# Power_Supply_Signal_Conditioning.net
KiCad netlist of a schematic drawn in Altium Designer
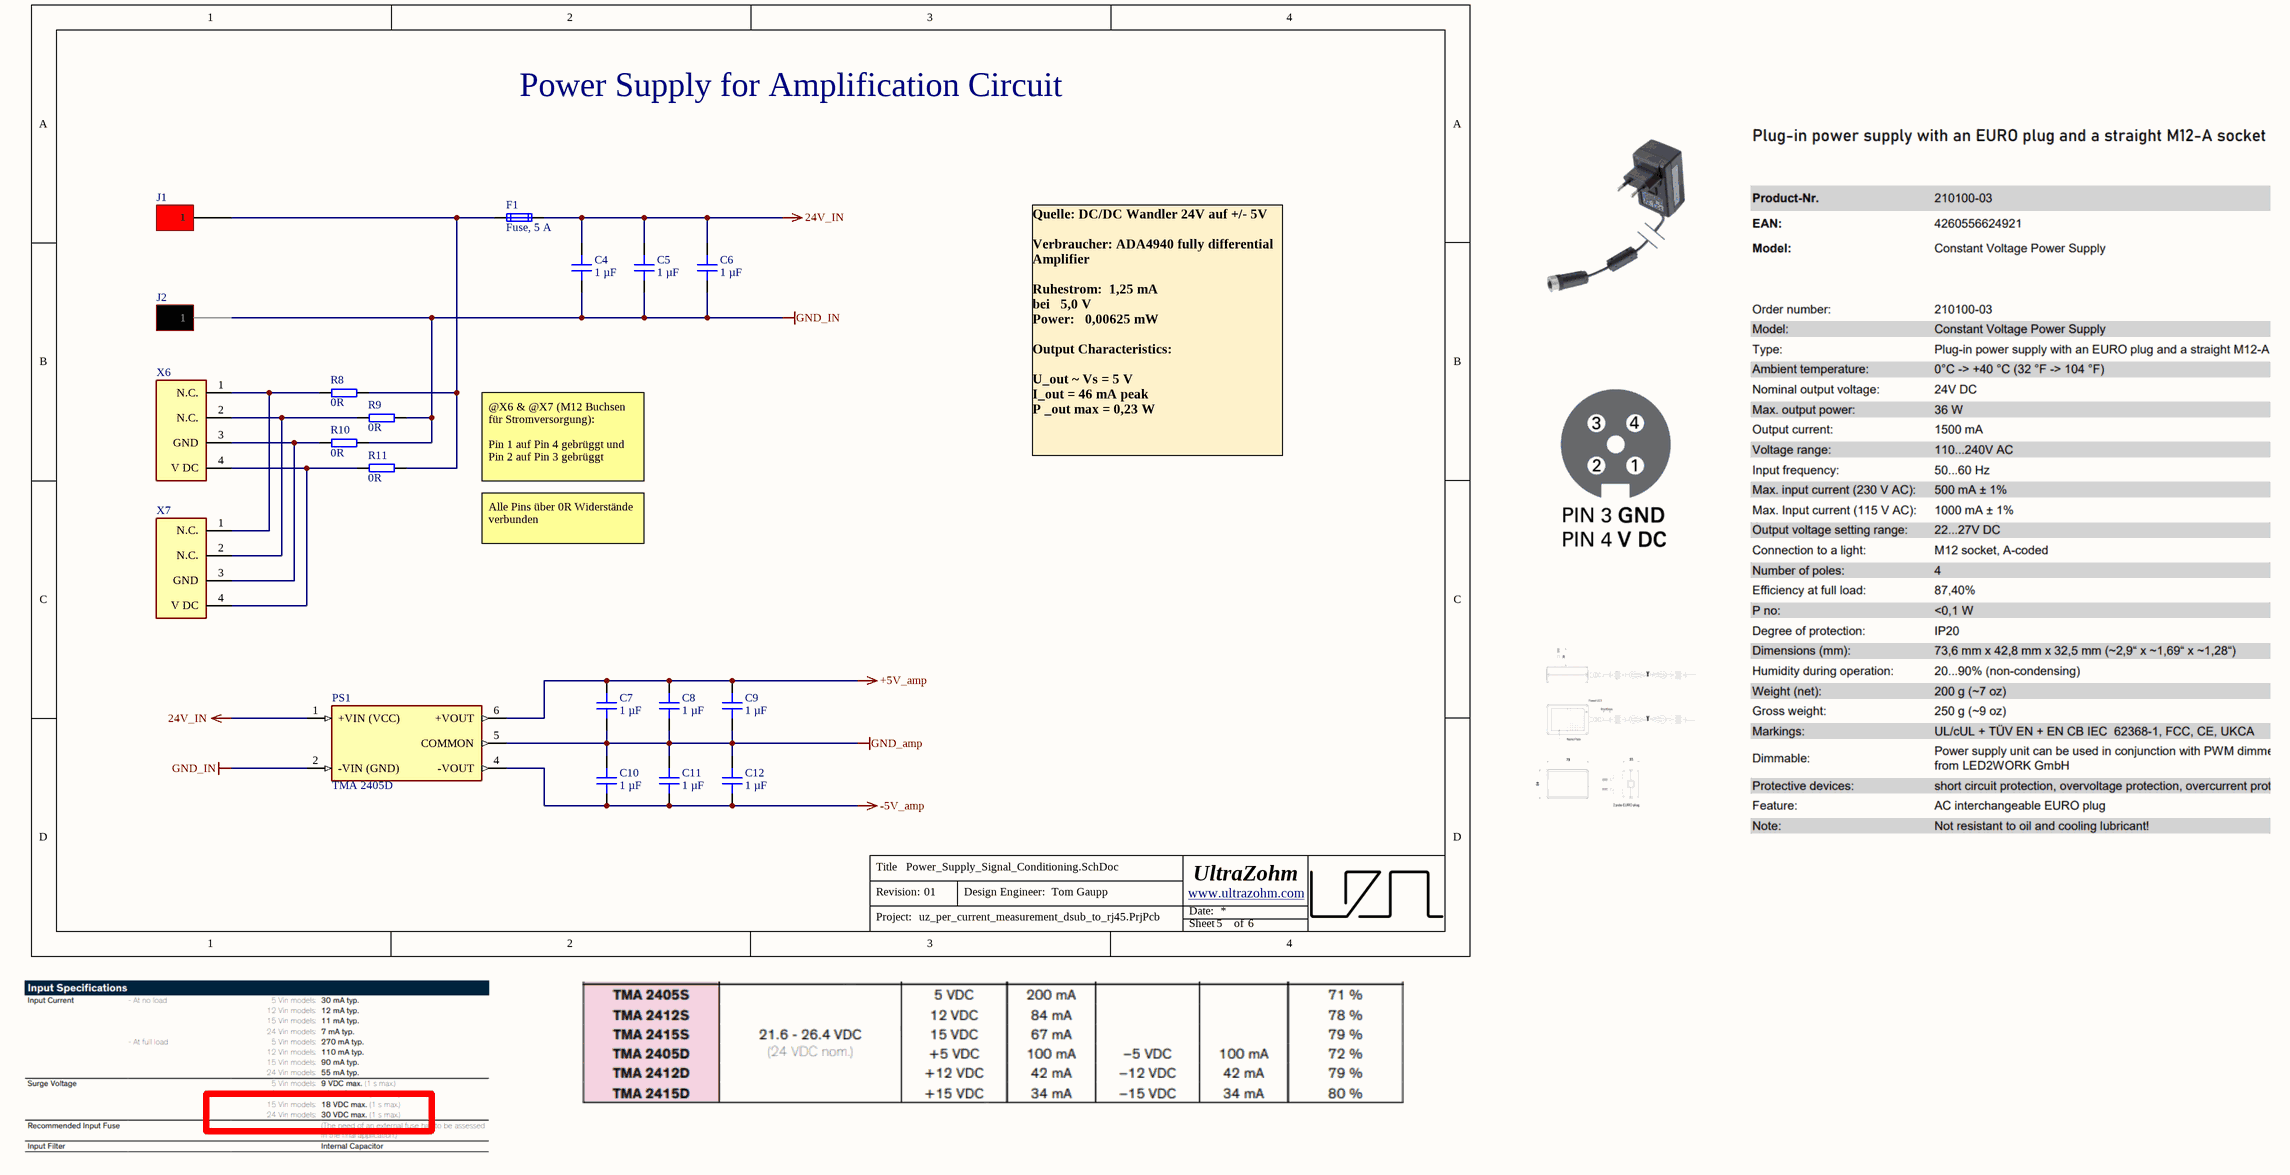
[diagram p0: Power_Supply_Signal_Conditioning.SchDoc]

(export (version "E")
  (design (tool "Eeschema 10.0.6"))
  (components
    (comp (ref "C4")
      (value "1 µF")
      (footprint "C_0603")
      (description "50V 1uF X5R ±10% 0603  Multilayer Ceramic Capacitors MLCC - SMD/SMT ROHS")
      (fields
        (field (name "MANUFACTURER") "Samsung Electro-Mechanics")
        (field (name "MANUFACTURER PART NUMBER") "CL10A105KB8NNNC")
        (field (name "CREATED FROM") "MGremer")
      )
      (libsource (lib "user") (part "Capacitor"))
    )
    (comp (ref "C5")
      (value "1 µF")
      (footprint "C_0603")
      (description "50V 1uF X5R ±10% 0603  Multilayer Ceramic Capacitors MLCC - SMD/SMT ROHS")
      (fields
        (field (name "MANUFACTURER") "Samsung Electro-Mechanics")
        (field (name "MANUFACTURER PART NUMBER") "CL10A105KB8NNNC")
        (field (name "CREATED FROM") "MGremer")
      )
      (libsource (lib "user") (part "Capacitor"))
    )
    (comp (ref "C6")
      (value "1 µF")
      (footprint "C_0603")
      (description "50V 1uF X5R ±10% 0603  Multilayer Ceramic Capacitors MLCC - SMD/SMT ROHS")
      (fields
        (field (name "MANUFACTURER") "Samsung Electro-Mechanics")
        (field (name "MANUFACTURER PART NUMBER") "CL10A105KB8NNNC")
        (field (name "CREATED FROM") "MGremer")
      )
      (libsource (lib "user") (part "Capacitor"))
    )
    (comp (ref "C7")
      (value "1 µF")
      (footprint "C_0603")
      (description "50V 1uF X5R ±10% 0603  Multilayer Ceramic Capacitors MLCC - SMD/SMT ROHS")
      (fields
        (field (name "MANUFACTURER") "Samsung Electro-Mechanics")
        (field (name "MANUFACTURER PART NUMBER") "CL10A105KB8NNNC")
        (field (name "CREATED FROM") "MGremer")
      )
      (libsource (lib "user") (part "Capacitor"))
    )
    (comp (ref "C8")
      (value "1 µF")
      (footprint "C_0603")
      (description "50V 1uF X5R ±10% 0603  Multilayer Ceramic Capacitors MLCC - SMD/SMT ROHS")
      (fields
        (field (name "MANUFACTURER") "Samsung Electro-Mechanics")
        (field (name "MANUFACTURER PART NUMBER") "CL10A105KB8NNNC")
        (field (name "CREATED FROM") "MGremer")
      )
      (libsource (lib "user") (part "Capacitor"))
    )
    (comp (ref "C9")
      (value "1 µF")
      (footprint "C_0603")
      (description "50V 1uF X5R ±10% 0603  Multilayer Ceramic Capacitors MLCC - SMD/SMT ROHS")
      (fields
        (field (name "MANUFACTURER") "Samsung Electro-Mechanics")
        (field (name "MANUFACTURER PART NUMBER") "CL10A105KB8NNNC")
        (field (name "CREATED FROM") "MGremer")
      )
      (libsource (lib "user") (part "Capacitor"))
    )
    (comp (ref "C10")
      (value "1 µF")
      (footprint "C_0603")
      (description "50V 1uF X5R ±10% 0603  Multilayer Ceramic Capacitors MLCC - SMD/SMT ROHS")
      (fields
        (field (name "MANUFACTURER") "Samsung Electro-Mechanics")
        (field (name "MANUFACTURER PART NUMBER") "CL10A105KB8NNNC")
        (field (name "CREATED FROM") "MGremer")
      )
      (libsource (lib "user") (part "Capacitor"))
    )
    (comp (ref "C11")
      (value "1 µF")
      (footprint "C_0603")
      (description "50V 1uF X5R ±10% 0603  Multilayer Ceramic Capacitors MLCC - SMD/SMT ROHS")
      (fields
        (field (name "MANUFACTURER") "Samsung Electro-Mechanics")
        (field (name "MANUFACTURER PART NUMBER") "CL10A105KB8NNNC")
        (field (name "CREATED FROM") "MGremer")
      )
      (libsource (lib "user") (part "Capacitor"))
    )
    (comp (ref "C12")
      (value "1 µF")
      (footprint "C_0603")
      (description "50V 1uF X5R ±10% 0603  Multilayer Ceramic Capacitors MLCC - SMD/SMT ROHS")
      (fields
        (field (name "MANUFACTURER") "Samsung Electro-Mechanics")
        (field (name "MANUFACTURER PART NUMBER") "CL10A105KB8NNNC")
        (field (name "CREATED FROM") "MGremer")
      )
      (libsource (lib "user") (part "Capacitor"))
    )
    (comp (ref "F1")
      (value "Fuse, 5 A")
      (footprint "0154xxx")
      (description "Fuse OMNI BLOK 154")
      (fields
        (field (name "MANUFACTURER PART NUMBER") "0154005.DR")
        (field (name "MANUFACTURER") "Littlefuse")
        (field (name "CREATED FROM") "MGremer")
      )
      (libsource (lib "user") (part "Polyswitch"))
    )
    (comp (ref "J1")
      (value "FCR7350R, PCB mount 4mm jack, RED")
      (footprint "FCR7350")
      (description "FCR7350B, 1000V, 24A, RED")
      (fields
        (field (name "MANUFACTURER PART NUMBER") "FCR7350R")
        (field (name "MANUFACTURER") "Cliff")
        (field (name "CREATED FROM") "DHufnagel")
      )
      (libsource (lib "user") (part "FCR7350R"))
    )
    (comp (ref "J2")
      (value "FCR7350B, PCB mount 4mm jack, BLACK")
      (footprint "FCR7350")
      (description "FCR7350B, 1000V, 24A, BLACK")
      (fields
        (field (name "MANUFACTURER PART NUMBER") "FCR7350B")
        (field (name "MANUFACTURER") "Cliff")
        (field (name "CREATED FROM") "DHufnagel")
      )
      (libsource (lib "user") (part "FCR7350B"))
    )
    (comp (ref "PS1")
      (value "TMA 2405D")
      (footprint "SIP7")
      (description "22-26 V Input, +/- 5 V @100mA  Output, 1 W, isolated DC/DC-converter")
      (fields
        (field (name "MANUFACTURER") "TRACO Power")
        (field (name "LCSC PART NUMBER") "C6285339")
        (field (name "CREATED FROM") "TGaupp")
      )
      (libsource (lib "user") (part "TMA2405D"))
    )
    (comp (ref "R8")
      (value "0R")
      (footprint "RES 1206_3216")
      (description "250mW Thick Film Resistors ±800ppm/℃ ±1% 0Ω 1206 Chip Resistor - Surface Mount ROHS")
      (fields
        (field (name "MANUFACTURER PART NUMBER") "1206W4F0000T5E")
        (field (name "MANUFACTURER") "UNI-ROYAL")
        (field (name "CREATED FROM") "AGeiger")
      )
      (libsource (lib "user") (part "Resistor"))
    )
    (comp (ref "R9")
      (value "0R")
      (footprint "RES 1206_3216")
      (description "250mW Thick Film Resistors ±800ppm/℃ ±1% 0Ω 1206 Chip Resistor - Surface Mount ROHS")
      (fields
        (field (name "MANUFACTURER PART NUMBER") "1206W4F0000T5E")
        (field (name "MANUFACTURER") "UNI-ROYAL")
        (field (name "CREATED FROM") "AGeiger")
      )
      (libsource (lib "user") (part "Resistor"))
    )
    (comp (ref "R10")
      (value "0R")
      (footprint "RES 1206_3216")
      (description "250mW Thick Film Resistors ±800ppm/℃ ±1% 0Ω 1206 Chip Resistor - Surface Mount ROHS")
      (fields
        (field (name "MANUFACTURER PART NUMBER") "1206W4F0000T5E")
        (field (name "MANUFACTURER") "UNI-ROYAL")
        (field (name "CREATED FROM") "AGeiger")
      )
      (libsource (lib "user") (part "Resistor"))
    )
    (comp (ref "R11")
      (value "0R")
      (footprint "RES 1206_3216")
      (description "250mW Thick Film Resistors ±800ppm/℃ ±1% 0Ω 1206 Chip Resistor - Surface Mount ROHS")
      (fields
        (field (name "MANUFACTURER PART NUMBER") "1206W4F0000T5E")
        (field (name "MANUFACTURER") "UNI-ROYAL")
        (field (name "CREATED FROM") "AGeiger")
      )
      (libsource (lib "user") (part "Resistor"))
    )
    (comp (ref "X6")
      (value "CAZN_M12-P4A-GPL_M12")
      (footprint "CAZN_M12-P4A-GPL_M12")
      (fields
        (field (name "MANUFACTURER") "CAZN")
        (field (name "LCSC PART NUMBER") "C19108992")
        (field (name "CREATED FROM") "TGaupp")
      )
      (libsource (lib "user") (part "CAZN_M12-P4A-GPL_M12"))
    )
    (comp (ref "X7")
      (value "CAZN_M12-P4A-GPL_M12")
      (footprint "CAZN_M12-P4A-GPL_M12")
      (fields
        (field (name "MANUFACTURER") "CAZN")
        (field (name "LCSC PART NUMBER") "C19108992")
        (field (name "CREATED FROM") "TGaupp")
      )
      (libsource (lib "user") (part "CAZN_M12-P4A-GPL_M12"))
    )
  )
  (nets
    (net (code "1") (name "+5V_amp") (class "Default")
      (node (ref "C7") (pin "2") (pinfunction "2_2") (pintype "passive"))
      (node (ref "C8") (pin "2") (pinfunction "2_2") (pintype "passive"))
      (node (ref "C9") (pin "2") (pinfunction "2_2") (pintype "passive"))
      (node (ref "PS1") (pin "6") (pinfunction "+VOUT_6") (pintype "output"))
    )
    (net (code "2") (name "-5V_amp") (class "Default")
      (node (ref "C10") (pin "1") (pinfunction "1_1") (pintype "passive"))
      (node (ref "C11") (pin "1") (pinfunction "1_1") (pintype "passive"))
      (node (ref "C12") (pin "1") (pinfunction "1_1") (pintype "passive"))
      (node (ref "PS1") (pin "4") (pinfunction "-VOUT_4") (pintype "output"))
    )
    (net (code "3") (name "24V_IN") (class "Default")
      (node (ref "C4") (pin "1") (pinfunction "1_1") (pintype "passive"))
      (node (ref "C5") (pin "1") (pinfunction "1_1") (pintype "passive"))
      (node (ref "C6") (pin "1") (pinfunction "1_1") (pintype "passive"))
      (node (ref "F1") (pin "2") (pinfunction "2_2") (pintype "passive"))
      (node (ref "PS1") (pin "1") (pinfunction "+VIN_(VCC)_1") (pintype "input"))
    )
    (net (code "4") (name "GND_IN") (class "Default")
      (node (ref "C4") (pin "2") (pinfunction "2_2") (pintype "passive"))
      (node (ref "C5") (pin "2") (pinfunction "2_2") (pintype "passive"))
      (node (ref "C6") (pin "2") (pinfunction "2_2") (pintype "passive"))
      (node (ref "J2") (pin "1") (pinfunction "1_1") (pintype "passive"))
      (node (ref "PS1") (pin "2") (pinfunction "-VIN_(GND)_2") (pintype "input"))
      (node (ref "R10") (pin "2") (pinfunction "2_2") (pintype "passive"))
      (node (ref "R9") (pin "2") (pinfunction "2_2") (pintype "passive"))
    )
    (net (code "5") (name "GND_amp") (class "Default")
      (node (ref "C10") (pin "2") (pinfunction "2_2") (pintype "passive"))
      (node (ref "C11") (pin "2") (pinfunction "2_2") (pintype "passive"))
      (node (ref "C12") (pin "2") (pinfunction "2_2") (pintype "passive"))
      (node (ref "C7") (pin "1") (pinfunction "1_1") (pintype "passive"))
      (node (ref "C8") (pin "1") (pinfunction "1_1") (pintype "passive"))
      (node (ref "C9") (pin "1") (pinfunction "1_1") (pintype "passive"))
      (node (ref "PS1") (pin "5") (pinfunction "COMMON_5") (pintype "output"))
    )
    (net (code "6") (name "Net-(F1-Pad1)") (class "Default")
      (node (ref "F1") (pin "1") (pinfunction "1_1") (pintype "passive"))
      (node (ref "J1") (pin "1") (pinfunction "1_1") (pintype "passive"))
      (node (ref "R11") (pin "2") (pinfunction "2_2") (pintype "passive"))
      (node (ref "R8") (pin "2") (pinfunction "2_2") (pintype "passive"))
    )
    (net (code "7") (name "Net-(R8-Pad1)") (class "Default")
      (node (ref "R8") (pin "1") (pinfunction "1_1") (pintype "passive"))
      (node (ref "X6") (pin "1") (pinfunction "N.C._1") (pintype "passive"))
      (node (ref "X7") (pin "1") (pinfunction "N.C._1") (pintype "passive"))
    )
    (net (code "8") (name "Net-(R9-Pad1)") (class "Default")
      (node (ref "R9") (pin "1") (pinfunction "1_1") (pintype "passive"))
      (node (ref "X6") (pin "2") (pinfunction "N.C._2") (pintype "passive"))
      (node (ref "X7") (pin "2") (pinfunction "N.C._2") (pintype "passive"))
    )
    (net (code "9") (name "Net-(X6-GND)") (class "Default")
      (node (ref "R10") (pin "1") (pinfunction "1_1") (pintype "passive"))
      (node (ref "X6") (pin "3") (pinfunction "GND_3") (pintype "power_in"))
      (node (ref "X7") (pin "3") (pinfunction "GND_3") (pintype "power_in"))
    )
    (net (code "10") (name "Net-(X6-V_DC)") (class "Default")
      (node (ref "R11") (pin "1") (pinfunction "1_1") (pintype "passive"))
      (node (ref "X6") (pin "4") (pinfunction "V_DC_4") (pintype "power_in"))
      (node (ref "X7") (pin "4") (pinfunction "V_DC_4") (pintype "power_in"))
    )
  )
)
